# Bank1_I_O_3.net
KiCad netlist of a schematic drawn in Altium Designer
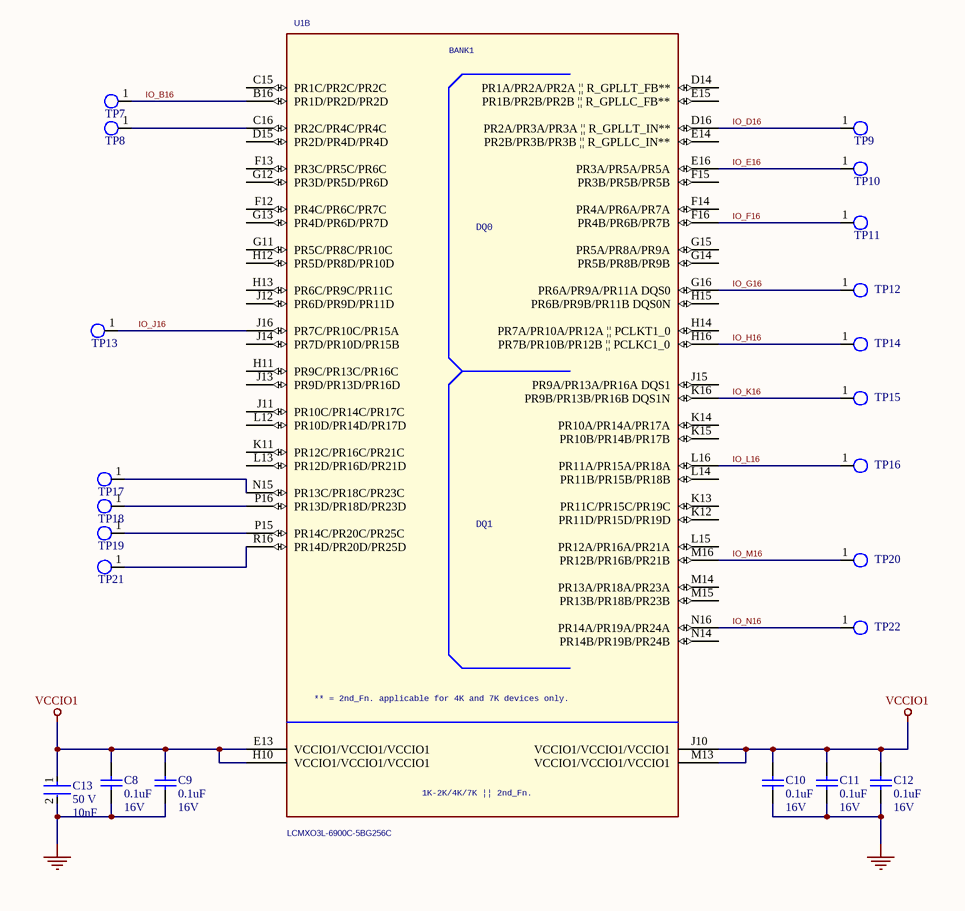
[diagram p0: Bank1_I_O 3.SchDoc]

(export (version "E")
  (design (tool "Eeschema 10.0.6"))
  (components
    (comp (ref "C8")
      (value "0.1uF")
      (footprint "CAPC1608X87X35ML15T15")
      (description "Ceramic Capacitor 0.1uF 16V +-10% X7R0603")
      (fields
        (field (name "PART NUMBER") "C0603C104M4RACTU")
        (field (name "MANUFACTURER") "Kemet")
        (field (name "VOLTAGE") "16V")
      )
      (libsource (lib "Altium Content Vault") (part "CAP"))
    )
    (comp (ref "C9")
      (value "0.1uF")
      (footprint "CAPC1608X87X35ML15T15")
      (description "Ceramic Capacitor 0.1uF 16V +-10% X7R0603")
      (fields
        (field (name "PART NUMBER") "C0603C104M4RACTU")
        (field (name "MANUFACTURER") "Kemet")
        (field (name "VOLTAGE") "16V")
      )
      (libsource (lib "Altium Content Vault") (part "CAP"))
    )
    (comp (ref "C10")
      (value "0.1uF")
      (footprint "CAPC1608X87X35ML15T15")
      (description "Ceramic Capacitor 0.1uF 16V +-10% X7R0603")
      (fields
        (field (name "PART NUMBER") "C0603C104M4RACTU")
        (field (name "MANUFACTURER") "Kemet")
        (field (name "VOLTAGE") "16V")
      )
      (libsource (lib "Altium Content Vault") (part "CAP"))
    )
    (comp (ref "C11")
      (value "0.1uF")
      (footprint "CAPC1608X87X35ML15T15")
      (description "Ceramic Capacitor 0.1uF 16V +-10% X7R0603")
      (fields
        (field (name "PART NUMBER") "C0603C104M4RACTU")
        (field (name "MANUFACTURER") "Kemet")
        (field (name "VOLTAGE") "16V")
      )
      (libsource (lib "Altium Content Vault") (part "CAP"))
    )
    (comp (ref "C12")
      (value "0.1uF")
      (footprint "CAPC1608X87X35ML15T15")
      (description "Ceramic Capacitor 0.1uF 16V +-10% X7R0603")
      (fields
        (field (name "PART NUMBER") "C0603C104M4RACTU")
        (field (name "MANUFACTURER") "Kemet")
        (field (name "VOLTAGE") "16V")
      )
      (libsource (lib "Altium Content Vault") (part "CAP"))
    )
    (comp (ref "C13")
      (value "10nF")
      (footprint "FP-C0805C-DN-MFG")
      (description "CAP CER 10000PF 50V X7R 0805")
      (fields
        (field (name "VOLTAGE") "50 V")
        (field (name "PART NUMBER") "C0805C103K5RACAUTO")
        (field (name "MANUFACTURER") "KEMET")
      )
      (libsource (lib "Altium Content Vault") (part "b4654b650e69147ec39a6b967a45e02"))
    )
    (comp (ref "TP7")
      (value "Test_Point_SMD")
      (footprint "Test_Point_SMD")
      (libsource (lib "Edson") (part "Test_Point_SMD"))
    )
    (comp (ref "TP8")
      (value "Test_Point_SMD")
      (footprint "Test_Point_SMD")
      (libsource (lib "Edson") (part "Test_Point_SMD"))
    )
    (comp (ref "TP9")
      (value "Test_Point_SMD")
      (footprint "Test_Point_SMD")
      (libsource (lib "Edson") (part "Test_Point_SMD"))
    )
    (comp (ref "TP10")
      (value "Test_Point_SMD")
      (footprint "Test_Point_SMD")
      (libsource (lib "Edson") (part "Test_Point_SMD"))
    )
    (comp (ref "TP11")
      (value "Test_Point_SMD")
      (footprint "Test_Point_SMD")
      (libsource (lib "Edson") (part "Test_Point_SMD"))
    )
    (comp (ref "TP12")
      (value "Test_Point_SMD")
      (footprint "Test_Point_SMD")
      (libsource (lib "Edson") (part "Test_Point_SMD"))
    )
    (comp (ref "TP13")
      (value "Test_Point_SMD")
      (footprint "Test_Point_SMD")
      (libsource (lib "Edson") (part "Test_Point_SMD"))
    )
    (comp (ref "TP14")
      (value "Test_Point_SMD")
      (footprint "Test_Point_SMD")
      (libsource (lib "Edson") (part "Test_Point_SMD"))
    )
    (comp (ref "TP15")
      (value "Test_Point_SMD")
      (footprint "Test_Point_SMD")
      (libsource (lib "Edson") (part "Test_Point_SMD"))
    )
    (comp (ref "TP16")
      (value "Test_Point_SMD")
      (footprint "Test_Point_SMD")
      (libsource (lib "Edson") (part "Test_Point_SMD"))
    )
    (comp (ref "TP17")
      (value "Test_Point_SMD")
      (footprint "Test_Point_SMD")
      (libsource (lib "Edson") (part "Test_Point_SMD"))
    )
    (comp (ref "TP18")
      (value "Test_Point_SMD")
      (footprint "Test_Point_SMD")
      (libsource (lib "Edson") (part "Test_Point_SMD"))
    )
    (comp (ref "TP19")
      (value "Test_Point_SMD")
      (footprint "Test_Point_SMD")
      (libsource (lib "Edson") (part "Test_Point_SMD"))
    )
    (comp (ref "TP20")
      (value "Test_Point_SMD")
      (footprint "Test_Point_SMD")
      (libsource (lib "Edson") (part "Test_Point_SMD"))
    )
    (comp (ref "TP21")
      (value "Test_Point_SMD")
      (footprint "Test_Point_SMD")
      (libsource (lib "Edson") (part "Test_Point_SMD"))
    )
    (comp (ref "TP22")
      (value "Test_Point_SMD")
      (footprint "Test_Point_SMD")
      (libsource (lib "Edson") (part "Test_Point_SMD"))
    )
    (comp (ref "U1")
      (value "LCMXO3L-6900C-5BG256C")
      (footprint "BGA256C80P16X16_1400X1400X170")
      (description "IC FPGA 6864LUTS 256BGA")
      (fields (field (name "MANUFACTURER") "Lattice semi"))
      (libsource (lib "*") (part "LCMXO3L-1K/2K/4K/7K-BG256"))
    )
  )
  (nets
    (net (code "1") (name "/IO_B16") (class "Default")
      (node (ref "TP7") (pin "1") (pinfunction "TP_1") (pintype "passive"))
      (node (ref "U1") (pin "B16") (pinfunction "PR1D/PR2D/PR2D_B16") (pintype "bidirectional"))
    )
    (net (code "2") (name "/IO_D16") (class "Default")
      (node (ref "TP9") (pin "1") (pinfunction "TP_1") (pintype "passive"))
      (node (ref "U1") (pin "D16") (pinfunction "PR2A/PR3A/PR3A_Ζ_R_GPLLT_IN**_D16") (pintype "bidirectional"))
    )
    (net (code "3") (name "/IO_E16") (class "Default")
      (node (ref "TP10") (pin "1") (pinfunction "TP_1") (pintype "passive"))
      (node (ref "U1") (pin "E16") (pinfunction "PR3A/PR5A/PR5A_E16") (pintype "bidirectional"))
    )
    (net (code "4") (name "/IO_F16") (class "Default")
      (node (ref "TP11") (pin "1") (pinfunction "TP_1") (pintype "passive"))
      (node (ref "U1") (pin "F16") (pinfunction "PR4B/PR6B/PR7B_F16") (pintype "bidirectional"))
    )
    (net (code "5") (name "/IO_G16") (class "Default")
      (node (ref "TP12") (pin "1") (pinfunction "TP_1") (pintype "passive"))
      (node (ref "U1") (pin "G16") (pinfunction "PR6A/PR9A/PR11A_DQS0_G16") (pintype "bidirectional"))
    )
    (net (code "6") (name "/IO_H16") (class "Default")
      (node (ref "TP14") (pin "1") (pinfunction "TP_1") (pintype "passive"))
      (node (ref "U1") (pin "H16") (pinfunction "PR7B/PR10B/PR12B_Ζ_PCLKC1_0_H16") (pintype "bidirectional"))
    )
    (net (code "7") (name "/IO_J16") (class "Default")
      (node (ref "TP13") (pin "1") (pinfunction "TP_1") (pintype "passive"))
      (node (ref "U1") (pin "J16") (pinfunction "PR7C/PR10C/PR15A_J16") (pintype "bidirectional"))
    )
    (net (code "8") (name "/IO_K16") (class "Default")
      (node (ref "TP15") (pin "1") (pinfunction "TP_1") (pintype "passive"))
      (node (ref "U1") (pin "K16") (pinfunction "PR9B/PR13B/PR16B_DQS1N_K16") (pintype "bidirectional"))
    )
    (net (code "9") (name "/IO_L16") (class "Default")
      (node (ref "TP16") (pin "1") (pinfunction "TP_1") (pintype "passive"))
      (node (ref "U1") (pin "L16") (pinfunction "PR11A/PR15A/PR18A_L16") (pintype "bidirectional"))
    )
    (net (code "10") (name "/IO_M16") (class "Default")
      (node (ref "TP20") (pin "1") (pinfunction "TP_1") (pintype "passive"))
      (node (ref "U1") (pin "M16") (pinfunction "PR12B/PR16B/PR21B_M16") (pintype "bidirectional"))
    )
    (net (code "11") (name "/IO_N16") (class "Default")
      (node (ref "TP22") (pin "1") (pinfunction "TP_1") (pintype "passive"))
      (node (ref "U1") (pin "N16") (pinfunction "PR14A/PR19A/PR24A_N16") (pintype "bidirectional"))
    )
    (net (code "12") (name "GND") (class "Default")
      (node (ref "C10") (pin "2") (pinfunction "2_2") (pintype "passive"))
      (node (ref "C11") (pin "2") (pinfunction "2_2") (pintype "passive"))
      (node (ref "C12") (pin "2") (pinfunction "2_2") (pintype "passive"))
      (node (ref "C13") (pin "2") (pinfunction "2_2") (pintype "passive"))
      (node (ref "C8") (pin "2") (pinfunction "2_2") (pintype "passive"))
      (node (ref "C9") (pin "2") (pinfunction "2_2") (pintype "passive"))
    )
    (net (code "13") (name "Net-(TP8-TP)") (class "Default")
      (node (ref "TP8") (pin "1") (pinfunction "TP_1") (pintype "passive"))
      (node (ref "U1") (pin "C16") (pinfunction "PR2C/PR4C/PR4C_C16") (pintype "bidirectional"))
    )
    (net (code "14") (name "Net-(TP17-TP)") (class "Default")
      (node (ref "TP17") (pin "1") (pinfunction "TP_1") (pintype "passive"))
      (node (ref "U1") (pin "N15") (pinfunction "PR13C/PR18C/PR23C_N15") (pintype "bidirectional"))
    )
    (net (code "15") (name "Net-(TP18-TP)") (class "Default")
      (node (ref "TP18") (pin "1") (pinfunction "TP_1") (pintype "passive"))
      (node (ref "U1") (pin "P16") (pinfunction "PR13D/PR18D/PR23D_P16") (pintype "bidirectional"))
    )
    (net (code "16") (name "Net-(TP19-TP)") (class "Default")
      (node (ref "TP19") (pin "1") (pinfunction "TP_1") (pintype "passive"))
      (node (ref "U1") (pin "P15") (pinfunction "PR14C/PR20C/PR25C_P15") (pintype "bidirectional"))
    )
    (net (code "17") (name "Net-(TP21-TP)") (class "Default")
      (node (ref "TP21") (pin "1") (pinfunction "TP_1") (pintype "passive"))
      (node (ref "U1") (pin "R16") (pinfunction "PR14D/PR20D/PR25D_R16") (pintype "bidirectional"))
    )
    (net (code "18") (name "VCCIO1") (class "Default")
      (node (ref "C10") (pin "1") (pinfunction "1_1") (pintype "passive"))
      (node (ref "C11") (pin "1") (pinfunction "1_1") (pintype "passive"))
      (node (ref "C12") (pin "1") (pinfunction "1_1") (pintype "passive"))
      (node (ref "C13") (pin "1") (pinfunction "1_1") (pintype "passive"))
      (node (ref "C8") (pin "1") (pinfunction "1_1") (pintype "passive"))
      (node (ref "C9") (pin "1") (pinfunction "1_1") (pintype "passive"))
      (node (ref "U1") (pin "E13") (pinfunction "VCCIO1/VCCIO1/VCCIO1_E13") (pintype "power_in"))
      (node (ref "U1") (pin "H10") (pinfunction "VCCIO1/VCCIO1/VCCIO1_H10") (pintype "power_in"))
      (node (ref "U1") (pin "J10") (pinfunction "VCCIO1/VCCIO1/VCCIO1_J10") (pintype "power_in"))
      (node (ref "U1") (pin "M13") (pinfunction "VCCIO1/VCCIO1/VCCIO1_M13") (pintype "power_in"))
    )
    (net (code "19") (name "unconnected-(U1B-PR1A{slash}PR2A{slash}PR2A_Ζ_R_GPLLT_FB**-PadD14)") (class "Default")
      (node (ref "U1") (pin "D14") (pinfunction "PR1A/PR2A/PR2A_Ζ_R_GPLLT_FB**_D14") (pintype "bidirectional"))
    )
    (net (code "20") (name "unconnected-(U1B-PR1B{slash}PR2B{slash}PR2B_Ζ_R_GPLLC_FB**-PadE15)") (class "Default")
      (node (ref "U1") (pin "E15") (pinfunction "PR1B/PR2B/PR2B_Ζ_R_GPLLC_FB**_E15") (pintype "bidirectional"))
    )
    (net (code "21") (name "unconnected-(U1B-PR1C{slash}PR2C{slash}PR2C-PadC15)") (class "Default")
      (node (ref "U1") (pin "C15") (pinfunction "PR1C/PR2C/PR2C_C15") (pintype "bidirectional"))
    )
    (net (code "22") (name "unconnected-(U1B-PR2B{slash}PR3B{slash}PR3B_Ζ_R_GPLLC_IN**-PadE14)") (class "Default")
      (node (ref "U1") (pin "E14") (pinfunction "PR2B/PR3B/PR3B_Ζ_R_GPLLC_IN**_E14") (pintype "bidirectional"))
    )
    (net (code "23") (name "unconnected-(U1B-PR2D{slash}PR4D{slash}PR4D-PadD15)") (class "Default")
      (node (ref "U1") (pin "D15") (pinfunction "PR2D/PR4D/PR4D_D15") (pintype "bidirectional"))
    )
    (net (code "24") (name "unconnected-(U1B-PR3B{slash}PR5B{slash}PR5B-PadF15)") (class "Default")
      (node (ref "U1") (pin "F15") (pinfunction "PR3B/PR5B/PR5B_F15") (pintype "bidirectional"))
    )
    (net (code "25") (name "unconnected-(U1B-PR3C{slash}PR5C{slash}PR6C-PadF13)") (class "Default")
      (node (ref "U1") (pin "F13") (pinfunction "PR3C/PR5C/PR6C_F13") (pintype "bidirectional"))
    )
    (net (code "26") (name "unconnected-(U1B-PR3D{slash}PR5D{slash}PR6D-PadG12)") (class "Default")
      (node (ref "U1") (pin "G12") (pinfunction "PR3D/PR5D/PR6D_G12") (pintype "bidirectional"))
    )
    (net (code "27") (name "unconnected-(U1B-PR4A{slash}PR6A{slash}PR7A-PadF14)") (class "Default")
      (node (ref "U1") (pin "F14") (pinfunction "PR4A/PR6A/PR7A_F14") (pintype "bidirectional"))
    )
    (net (code "28") (name "unconnected-(U1B-PR4C{slash}PR6C{slash}PR7C-PadF12)") (class "Default")
      (node (ref "U1") (pin "F12") (pinfunction "PR4C/PR6C/PR7C_F12") (pintype "bidirectional"))
    )
    (net (code "29") (name "unconnected-(U1B-PR4D{slash}PR6D{slash}PR7D-PadG13)") (class "Default")
      (node (ref "U1") (pin "G13") (pinfunction "PR4D/PR6D/PR7D_G13") (pintype "bidirectional"))
    )
    (net (code "30") (name "unconnected-(U1B-PR5A{slash}PR8A{slash}PR9A-PadG15)") (class "Default")
      (node (ref "U1") (pin "G15") (pinfunction "PR5A/PR8A/PR9A_G15") (pintype "bidirectional"))
    )
    (net (code "31") (name "unconnected-(U1B-PR5B{slash}PR8B{slash}PR9B-PadG14)") (class "Default")
      (node (ref "U1") (pin "G14") (pinfunction "PR5B/PR8B/PR9B_G14") (pintype "bidirectional"))
    )
    (net (code "32") (name "unconnected-(U1B-PR5C{slash}PR8C{slash}PR10C-PadG11)") (class "Default")
      (node (ref "U1") (pin "G11") (pinfunction "PR5C/PR8C/PR10C_G11") (pintype "bidirectional"))
    )
    (net (code "33") (name "unconnected-(U1B-PR5D{slash}PR8D{slash}PR10D-PadH12)") (class "Default")
      (node (ref "U1") (pin "H12") (pinfunction "PR5D/PR8D/PR10D_H12") (pintype "bidirectional"))
    )
    (net (code "34") (name "unconnected-(U1B-PR6B{slash}PR9B{slash}PR11B_DQS0N-PadH15)") (class "Default")
      (node (ref "U1") (pin "H15") (pinfunction "PR6B/PR9B/PR11B_DQS0N_H15") (pintype "bidirectional"))
    )
    (net (code "35") (name "unconnected-(U1B-PR6C{slash}PR9C{slash}PR11C-PadH13)") (class "Default")
      (node (ref "U1") (pin "H13") (pinfunction "PR6C/PR9C/PR11C_H13") (pintype "bidirectional"))
    )
    (net (code "36") (name "unconnected-(U1B-PR6D{slash}PR9D{slash}PR11D-PadJ12)") (class "Default")
      (node (ref "U1") (pin "J12") (pinfunction "PR6D/PR9D/PR11D_J12") (pintype "bidirectional"))
    )
    (net (code "37") (name "unconnected-(U1B-PR7A{slash}PR10A{slash}PR12A_Ζ_PCLKT1_0-PadH14)") (class "Default")
      (node (ref "U1") (pin "H14") (pinfunction "PR7A/PR10A/PR12A_Ζ_PCLKT1_0_H14") (pintype "bidirectional"))
    )
    (net (code "38") (name "unconnected-(U1B-PR7D{slash}PR10D{slash}PR15B-PadJ14)") (class "Default")
      (node (ref "U1") (pin "J14") (pinfunction "PR7D/PR10D/PR15B_J14") (pintype "bidirectional"))
    )
    (net (code "39") (name "unconnected-(U1B-PR9A{slash}PR13A{slash}PR16A_DQS1-PadJ15)") (class "Default")
      (node (ref "U1") (pin "J15") (pinfunction "PR9A/PR13A/PR16A_DQS1_J15") (pintype "bidirectional"))
    )
    (net (code "40") (name "unconnected-(U1B-PR9C{slash}PR13C{slash}PR16C-PadH11)") (class "Default")
      (node (ref "U1") (pin "H11") (pinfunction "PR9C/PR13C/PR16C_H11") (pintype "bidirectional"))
    )
    (net (code "41") (name "unconnected-(U1B-PR9D{slash}PR13D{slash}PR16D-PadJ13)") (class "Default")
      (node (ref "U1") (pin "J13") (pinfunction "PR9D/PR13D/PR16D_J13") (pintype "bidirectional"))
    )
    (net (code "42") (name "unconnected-(U1B-PR10A{slash}PR14A{slash}PR17A-PadK14)") (class "Default")
      (node (ref "U1") (pin "K14") (pinfunction "PR10A/PR14A/PR17A_K14") (pintype "bidirectional"))
    )
    (net (code "43") (name "unconnected-(U1B-PR10B{slash}PR14B{slash}PR17B-PadK15)") (class "Default")
      (node (ref "U1") (pin "K15") (pinfunction "PR10B/PR14B/PR17B_K15") (pintype "bidirectional"))
    )
    (net (code "44") (name "unconnected-(U1B-PR10C{slash}PR14C{slash}PR17C-PadJ11)") (class "Default")
      (node (ref "U1") (pin "J11") (pinfunction "PR10C/PR14C/PR17C_J11") (pintype "bidirectional"))
    )
    (net (code "45") (name "unconnected-(U1B-PR10D{slash}PR14D{slash}PR17D-PadL12)") (class "Default")
      (node (ref "U1") (pin "L12") (pinfunction "PR10D/PR14D/PR17D_L12") (pintype "bidirectional"))
    )
    (net (code "46") (name "unconnected-(U1B-PR11B{slash}PR15B{slash}PR18B-PadL14)") (class "Default")
      (node (ref "U1") (pin "L14") (pinfunction "PR11B/PR15B/PR18B_L14") (pintype "bidirectional"))
    )
    (net (code "47") (name "unconnected-(U1B-PR11C{slash}PR15C{slash}PR19C-PadK13)") (class "Default")
      (node (ref "U1") (pin "K13") (pinfunction "PR11C/PR15C/PR19C_K13") (pintype "bidirectional"))
    )
    (net (code "48") (name "unconnected-(U1B-PR11D{slash}PR15D{slash}PR19D-PadK12)") (class "Default")
      (node (ref "U1") (pin "K12") (pinfunction "PR11D/PR15D/PR19D_K12") (pintype "bidirectional"))
    )
    (net (code "49") (name "unconnected-(U1B-PR12A{slash}PR16A{slash}PR21A-PadL15)") (class "Default")
      (node (ref "U1") (pin "L15") (pinfunction "PR12A/PR16A/PR21A_L15") (pintype "bidirectional"))
    )
    (net (code "50") (name "unconnected-(U1B-PR12C{slash}PR16C{slash}PR21C-PadK11)") (class "Default")
      (node (ref "U1") (pin "K11") (pinfunction "PR12C/PR16C/PR21C_K11") (pintype "bidirectional"))
    )
    (net (code "51") (name "unconnected-(U1B-PR12D{slash}PR16D{slash}PR21D-PadL13)") (class "Default")
      (node (ref "U1") (pin "L13") (pinfunction "PR12D/PR16D/PR21D_L13") (pintype "bidirectional"))
    )
    (net (code "52") (name "unconnected-(U1B-PR13A{slash}PR18A{slash}PR23A-PadM14)") (class "Default")
      (node (ref "U1") (pin "M14") (pinfunction "PR13A/PR18A/PR23A_M14") (pintype "bidirectional"))
    )
    (net (code "53") (name "unconnected-(U1B-PR13B{slash}PR18B{slash}PR23B-PadM15)") (class "Default")
      (node (ref "U1") (pin "M15") (pinfunction "PR13B/PR18B/PR23B_M15") (pintype "bidirectional"))
    )
    (net (code "54") (name "unconnected-(U1B-PR14B{slash}PR19B{slash}PR24B-PadN14)") (class "Default")
      (node (ref "U1") (pin "N14") (pinfunction "PR14B/PR19B/PR24B_N14") (pintype "bidirectional"))
    )
  )
)
